# S_bus.net
KiCad netlist of a schematic drawn in Altium Designer
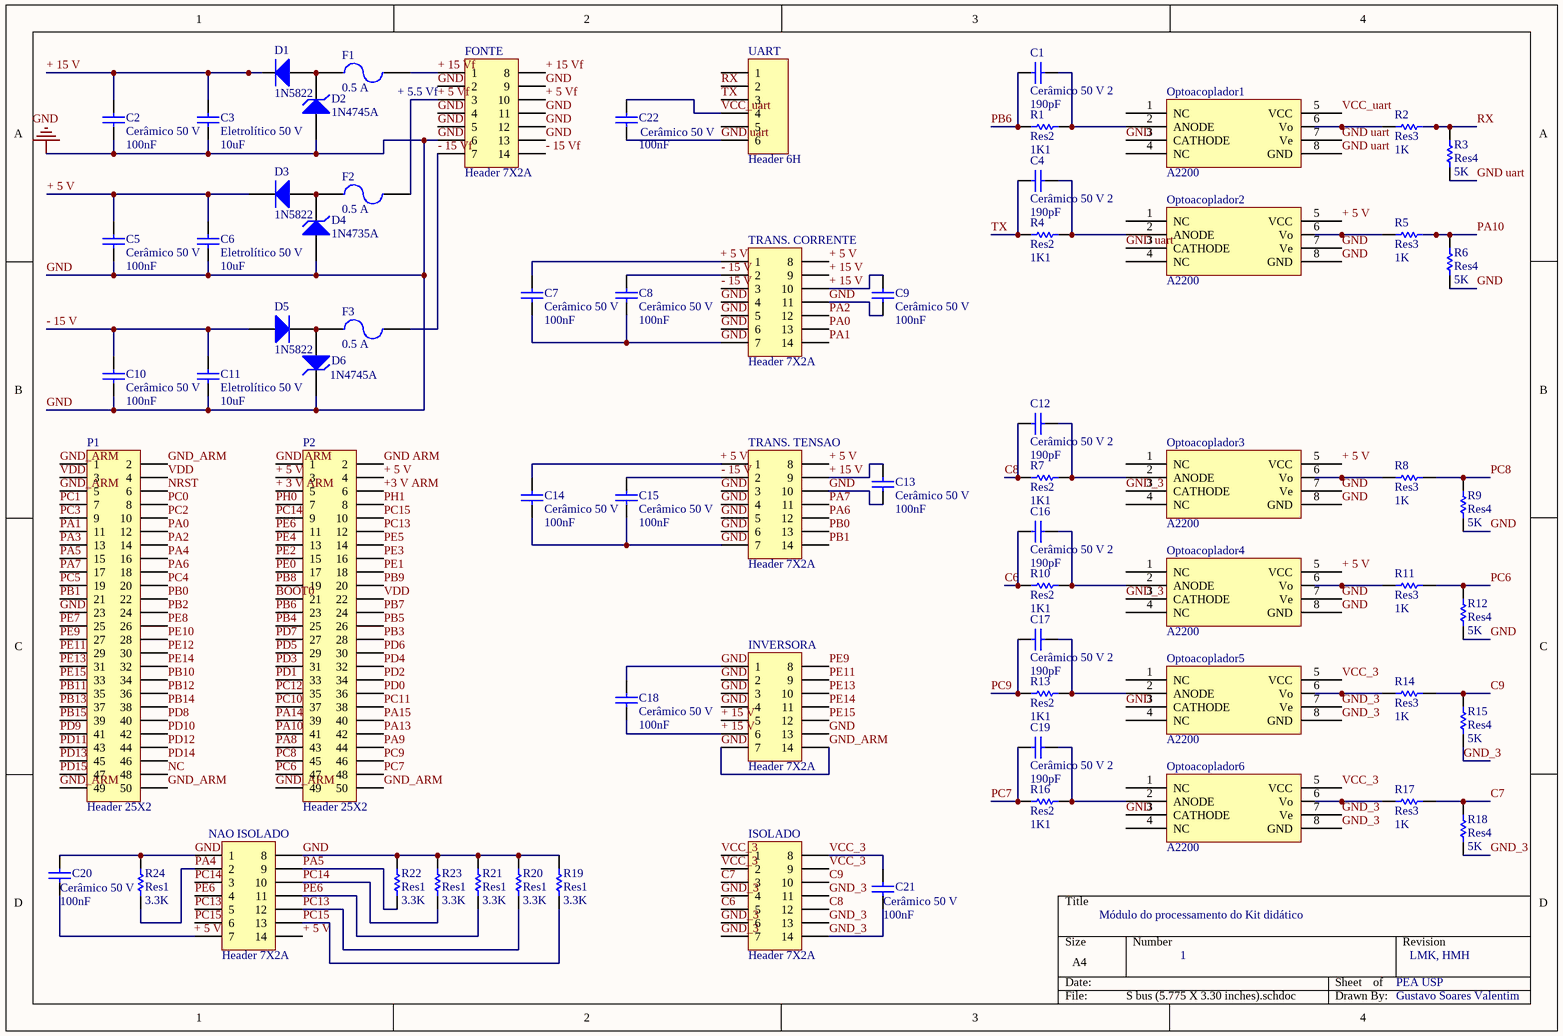
[diagram p0: S bus (5.775 X 3.30 inches).schdoc]

(export (version "E")
  (design (tool "Eeschema 10.0.6"))
  (components
    (comp (ref "C1")
      (value "Cerâmico 50 V 2")
      (footprint "RAD-0.2")
      (description "Capacitor")
      (fields (field (name "ALTIUM_VALUE") "190pF") (field (name "PUBLISHER") "Altium Limited"))
      (libsource (lib "Miscellaneous Devices") (part "Cap"))
    )
    (comp (ref "C2")
      (value "Cerâmico 50 V")
      (footprint "RAD-0.2")
      (description "Capacitor")
      (fields (field (name "ALTIUM_VALUE") "100nF") (field (name "PUBLISHER") "Altium Limited"))
      (libsource (lib "Miscellaneous Devices") (part "Cap"))
    )
    (comp (ref "C3")
      (value "Eletrolítico 50 V")
      (footprint "RB5-10.5")
      (description "Capacitor")
      (fields (field (name "ALTIUM_VALUE") "10uF") (field (name "PUBLISHER") "Altium Limited"))
      (libsource (lib "Miscellaneous Devices") (part "Cap"))
    )
    (comp (ref "C4")
      (value "Cerâmico 50 V 2")
      (footprint "RAD-0.2")
      (description "Capacitor")
      (fields (field (name "ALTIUM_VALUE") "190pF") (field (name "PUBLISHER") "Altium Limited"))
      (libsource (lib "Miscellaneous Devices") (part "Cap"))
    )
    (comp (ref "C5")
      (value "Cerâmico 50 V")
      (footprint "RAD-0.2")
      (description "Capacitor")
      (fields (field (name "ALTIUM_VALUE") "100nF") (field (name "PUBLISHER") "Altium Limited"))
      (libsource (lib "Miscellaneous Devices") (part "Cap"))
    )
    (comp (ref "C6")
      (value "Eletrolítico 50 V")
      (footprint "RB5-10.5")
      (description "Capacitor")
      (fields (field (name "ALTIUM_VALUE") "10uF") (field (name "PUBLISHER") "Altium Limited"))
      (libsource (lib "Miscellaneous Devices") (part "Cap"))
    )
    (comp (ref "C7")
      (value "Cerâmico 50 V")
      (footprint "RAD-0.2")
      (description "Capacitor")
      (fields (field (name "ALTIUM_VALUE") "100nF") (field (name "PUBLISHER") "Altium Limited"))
      (libsource (lib "Miscellaneous Devices") (part "Cap"))
    )
    (comp (ref "C8")
      (value "Cerâmico 50 V")
      (footprint "RAD-0.2")
      (description "Capacitor")
      (fields (field (name "ALTIUM_VALUE") "100nF") (field (name "PUBLISHER") "Altium Limited"))
      (libsource (lib "Miscellaneous Devices") (part "Cap"))
    )
    (comp (ref "C9")
      (value "Cerâmico 50 V")
      (footprint "RAD-0.2")
      (description "Capacitor")
      (fields (field (name "ALTIUM_VALUE") "100nF") (field (name "PUBLISHER") "Altium Limited"))
      (libsource (lib "Miscellaneous Devices") (part "Cap"))
    )
    (comp (ref "C10")
      (value "Cerâmico 50 V")
      (footprint "RAD-0.2")
      (description "Capacitor")
      (fields (field (name "ALTIUM_VALUE") "100nF") (field (name "PUBLISHER") "Altium Limited"))
      (libsource (lib "Miscellaneous Devices") (part "Cap"))
    )
    (comp (ref "C11")
      (value "Eletrolítico 50 V")
      (footprint "RB5-10.5")
      (description "Capacitor")
      (fields (field (name "ALTIUM_VALUE") "10uF") (field (name "PUBLISHER") "Altium Limited"))
      (libsource (lib "Miscellaneous Devices") (part "Cap"))
    )
    (comp (ref "C12")
      (value "Cerâmico 50 V 2")
      (footprint "RAD-0.2")
      (description "Capacitor")
      (fields (field (name "ALTIUM_VALUE") "190pF") (field (name "PUBLISHER") "Altium Limited"))
      (libsource (lib "Miscellaneous Devices") (part "Cap"))
    )
    (comp (ref "C13")
      (value "Cerâmico 50 V")
      (footprint "RAD-0.2")
      (description "Capacitor")
      (fields (field (name "ALTIUM_VALUE") "100nF") (field (name "PUBLISHER") "Altium Limited"))
      (libsource (lib "Miscellaneous Devices") (part "Cap"))
    )
    (comp (ref "C14")
      (value "Cerâmico 50 V")
      (footprint "RAD-0.2")
      (description "Capacitor")
      (fields (field (name "ALTIUM_VALUE") "100nF") (field (name "PUBLISHER") "Altium Limited"))
      (libsource (lib "Miscellaneous Devices") (part "Cap"))
    )
    (comp (ref "C15")
      (value "Cerâmico 50 V")
      (footprint "RAD-0.2")
      (description "Capacitor")
      (fields (field (name "ALTIUM_VALUE") "100nF") (field (name "PUBLISHER") "Altium Limited"))
      (libsource (lib "Miscellaneous Devices") (part "Cap"))
    )
    (comp (ref "C16")
      (value "Cerâmico 50 V 2")
      (footprint "RAD-0.2")
      (description "Capacitor")
      (fields (field (name "ALTIUM_VALUE") "190pF") (field (name "PUBLISHER") "Altium Limited"))
      (libsource (lib "Miscellaneous Devices") (part "Cap"))
    )
    (comp (ref "C17")
      (value "Cerâmico 50 V 2")
      (footprint "RAD-0.2")
      (description "Capacitor")
      (fields (field (name "ALTIUM_VALUE") "190pF") (field (name "PUBLISHER") "Altium Limited"))
      (libsource (lib "Miscellaneous Devices") (part "Cap"))
    )
    (comp (ref "C18")
      (value "Cerâmico 50 V")
      (footprint "RAD-0.2")
      (description "Capacitor")
      (fields (field (name "ALTIUM_VALUE") "100nF") (field (name "PUBLISHER") "Altium Limited"))
      (libsource (lib "Miscellaneous Devices") (part "Cap"))
    )
    (comp (ref "C19")
      (value "Cerâmico 50 V 2")
      (footprint "RAD-0.2")
      (description "Capacitor")
      (fields (field (name "ALTIUM_VALUE") "190pF") (field (name "PUBLISHER") "Altium Limited"))
      (libsource (lib "Miscellaneous Devices") (part "Cap"))
    )
    (comp (ref "C20")
      (value "Cerâmico 50 V")
      (footprint "RAD-0.2")
      (description "Capacitor")
      (fields (field (name "ALTIUM_VALUE") "100nF") (field (name "PUBLISHER") "Altium Limited"))
      (libsource (lib "Miscellaneous Devices") (part "Cap"))
    )
    (comp (ref "C21")
      (value "Cerâmico 50 V")
      (footprint "RAD-0.2")
      (description "Capacitor")
      (fields (field (name "ALTIUM_VALUE") "100nF") (field (name "PUBLISHER") "Altium Limited"))
      (libsource (lib "Miscellaneous Devices") (part "Cap"))
    )
    (comp (ref "C22")
      (value "Cerâmico 50 V")
      (footprint "RAD-0.2")
      (description "Capacitor")
      (fields (field (name "ALTIUM_VALUE") "100nF") (field (name "PUBLISHER") "Altium Limited"))
      (libsource (lib "Miscellaneous Devices") (part "Cap"))
    )
    (comp (ref "D1")
      (value "1N5822")
      (footprint "AXIAL-0.4")
      (description "Default Diode")
      (fields (field (name "PUBLISHER") "Altium Limited"))
      (libsource (lib "Miscellaneous Devices") (part "Diode"))
    )
    (comp (ref "D2")
      (value "1N4745A")
      (footprint "DIODE-0.4")
      (description "Zener Diode")
      (fields (field (name "PUBLISHER") "Altium Limited"))
      (libsource (lib "Miscellaneous Devices") (part "D Zener"))
    )
    (comp (ref "D3")
      (value "1N5822")
      (footprint "AXIAL-0.4")
      (description "Default Diode")
      (fields (field (name "PUBLISHER") "Altium Limited"))
      (libsource (lib "Miscellaneous Devices") (part "Diode"))
    )
    (comp (ref "D4")
      (value "1N4735A")
      (footprint "DIODE-0.4")
      (description "Zener Diode")
      (fields (field (name "PUBLISHER") "Altium Limited"))
      (libsource (lib "Miscellaneous Devices") (part "D Zener"))
    )
    (comp (ref "D5")
      (value "1N5822")
      (footprint "AXIAL-0.4")
      (description "Default Diode")
      (fields (field (name "PUBLISHER") "Altium Limited"))
      (libsource (lib "Miscellaneous Devices") (part "Diode"))
    )
    (comp (ref "D6")
      (value "1N4745A")
      (footprint "DIODE-0.4")
      (description "Zener Diode")
      (fields (field (name "PUBLISHER") "Altium Limited"))
      (libsource (lib "Miscellaneous Devices") (part "D Zener"))
    )
    (comp (ref "F1")
      (value "0.5 A")
      (footprint "Fusivel")
      (description "Fuse")
      (fields (field (name "PUBLISHER") "Altium Limited"))
      (libsource (lib "Miscellaneous Devices") (part "Fuse 2"))
    )
    (comp (ref "F2")
      (value "0.5 A")
      (footprint "Fusivel")
      (description "Fuse")
      (fields (field (name "PUBLISHER") "Altium Limited"))
      (libsource (lib "Miscellaneous Devices") (part "Fuse 2"))
    )
    (comp (ref "F3")
      (value "0.5 A")
      (footprint "Fusivel")
      (description "Fuse")
      (fields (field (name "PUBLISHER") "Altium Limited"))
      (libsource (lib "Miscellaneous Devices") (part "Fuse 2"))
    )
    (comp (ref "FONTE")
      (value "Header 7X2A")
      (footprint "HDR2X7_CEN")
      (description "Header, 7-Pin, Dual row")
      (fields (field (name "PUBLISHER") "Altium Limited"))
      (libsource (lib "Miscellaneous Connectors") (part "Header 7X2A"))
    )
    (comp (ref "INVERSORA")
      (value "Header 7X2A")
      (footprint "HDR2X7_CEN")
      (description "Header, 7-Pin, Dual row")
      (fields (field (name "PUBLISHER") "Altium Limited"))
      (libsource (lib "Miscellaneous Connectors") (part "Header 7X2A"))
    )
    (comp (ref "ISOLADO")
      (value "Header 7X2A")
      (footprint "HDR2X7_CEN")
      (description "Header, 7-Pin, Dual row")
      (fields (field (name "PUBLISHER") "Altium Limited"))
      (libsource (lib "Miscellaneous Connectors") (part "Header 7X2A"))
    )
    (comp (ref "NAO ISOLADO")
      (value "Header 7X2A")
      (footprint "HDR2X7_CEN")
      (description "Header, 7-Pin, Dual row")
      (fields (field (name "PUBLISHER") "Altium Limited"))
      (libsource (lib "Miscellaneous Connectors") (part "Header 7X2A"))
    )
    (comp (ref "Optoacoplador1")
      (value "A2200")
      (footprint "DIP8")
      (libsource (lib "optoacoplador") (part "Optoacoplador"))
    )
    (comp (ref "Optoacoplador2")
      (value "A2200")
      (footprint "DIP8")
      (libsource (lib "optoacoplador") (part "Optoacoplador"))
    )
    (comp (ref "Optoacoplador3")
      (value "A2200")
      (footprint "DIP8")
      (libsource (lib "optoacoplador") (part "Optoacoplador"))
    )
    (comp (ref "Optoacoplador4")
      (value "A2200")
      (footprint "DIP8")
      (libsource (lib "optoacoplador") (part "Optoacoplador"))
    )
    (comp (ref "Optoacoplador5")
      (value "A2200")
      (footprint "DIP8")
      (libsource (lib "optoacoplador") (part "Optoacoplador"))
    )
    (comp (ref "Optoacoplador6")
      (value "A2200")
      (footprint "DIP8")
      (libsource (lib "optoacoplador") (part "Optoacoplador"))
    )
    (comp (ref "P1")
      (value "Header 25X2")
      (footprint "HDR2X25")
      (description "Header, 25-Pin, Dual row")
      (fields (field (name "PUBLISHER") "Altium Limited"))
      (libsource (lib "Miscellaneous Connectors") (part "Header 25X2"))
    )
    (comp (ref "P2")
      (value "Header 25X2")
      (footprint "HDR2X25")
      (description "Header, 25-Pin, Dual row")
      (fields (field (name "PUBLISHER") "Altium Limited"))
      (libsource (lib "Miscellaneous Connectors") (part "Header 25X2"))
    )
    (comp (ref "R1")
      (value "Res2")
      (footprint "AXIAL-0.3")
      (description "Resistor")
      (fields (field (name "ALTIUM_VALUE") "1K1") (field (name "PUBLISHER") "Altium Limited"))
      (libsource (lib "Miscellaneous Devices") (part "Res1"))
    )
    (comp (ref "R2")
      (value "Res3")
      (footprint "AXIAL-0.3")
      (description "Resistor")
      (fields (field (name "ALTIUM_VALUE") "1K") (field (name "PUBLISHER") "Altium Limited"))
      (libsource (lib "Miscellaneous Devices") (part "Res1"))
    )
    (comp (ref "R3")
      (value "Res4")
      (footprint "AXIAL-0.3")
      (description "Resistor")
      (fields (field (name "ALTIUM_VALUE") "5K") (field (name "PUBLISHER") "Altium Limited"))
      (libsource (lib "Miscellaneous Devices") (part "Res1"))
    )
    (comp (ref "R4")
      (value "Res2")
      (footprint "AXIAL-0.3")
      (description "Resistor")
      (fields (field (name "ALTIUM_VALUE") "1K1") (field (name "PUBLISHER") "Altium Limited"))
      (libsource (lib "Miscellaneous Devices") (part "Res1"))
    )
    (comp (ref "R5")
      (value "Res3")
      (footprint "AXIAL-0.3")
      (description "Resistor")
      (fields (field (name "ALTIUM_VALUE") "1K") (field (name "PUBLISHER") "Altium Limited"))
      (libsource (lib "Miscellaneous Devices") (part "Res1"))
    )
    (comp (ref "R6")
      (value "Res4")
      (footprint "AXIAL-0.3")
      (description "Resistor")
      (fields (field (name "ALTIUM_VALUE") "5K") (field (name "PUBLISHER") "Altium Limited"))
      (libsource (lib "Miscellaneous Devices") (part "Res1"))
    )
    (comp (ref "R7")
      (value "Res2")
      (footprint "AXIAL-0.3")
      (description "Resistor")
      (fields (field (name "ALTIUM_VALUE") "1K1") (field (name "PUBLISHER") "Altium Limited"))
      (libsource (lib "Miscellaneous Devices") (part "Res1"))
    )
    (comp (ref "R8")
      (value "Res3")
      (footprint "AXIAL-0.3")
      (description "Resistor")
      (fields (field (name "ALTIUM_VALUE") "1K") (field (name "PUBLISHER") "Altium Limited"))
      (libsource (lib "Miscellaneous Devices") (part "Res1"))
    )
    (comp (ref "R9")
      (value "Res4")
      (footprint "AXIAL-0.3")
      (description "Resistor")
      (fields (field (name "ALTIUM_VALUE") "5K") (field (name "PUBLISHER") "Altium Limited"))
      (libsource (lib "Miscellaneous Devices") (part "Res1"))
    )
    (comp (ref "R10")
      (value "Res2")
      (footprint "AXIAL-0.3")
      (description "Resistor")
      (fields (field (name "ALTIUM_VALUE") "1K1") (field (name "PUBLISHER") "Altium Limited"))
      (libsource (lib "Miscellaneous Devices") (part "Res1"))
    )
    (comp (ref "R11")
      (value "Res3")
      (footprint "AXIAL-0.3")
      (description "Resistor")
      (fields (field (name "ALTIUM_VALUE") "1K") (field (name "PUBLISHER") "Altium Limited"))
      (libsource (lib "Miscellaneous Devices") (part "Res1"))
    )
    (comp (ref "R12")
      (value "Res4")
      (footprint "AXIAL-0.3")
      (description "Resistor")
      (fields (field (name "ALTIUM_VALUE") "5K") (field (name "PUBLISHER") "Altium Limited"))
      (libsource (lib "Miscellaneous Devices") (part "Res1"))
    )
    (comp (ref "R13")
      (value "Res2")
      (footprint "AXIAL-0.3")
      (description "Resistor")
      (fields (field (name "ALTIUM_VALUE") "1K1") (field (name "PUBLISHER") "Altium Limited"))
      (libsource (lib "Miscellaneous Devices") (part "Res1"))
    )
    (comp (ref "R14")
      (value "Res3")
      (footprint "AXIAL-0.3")
      (description "Resistor")
      (fields (field (name "ALTIUM_VALUE") "1K") (field (name "PUBLISHER") "Altium Limited"))
      (libsource (lib "Miscellaneous Devices") (part "Res1"))
    )
    (comp (ref "R15")
      (value "Res4")
      (footprint "AXIAL-0.3")
      (description "Resistor")
      (fields (field (name "ALTIUM_VALUE") "5K") (field (name "PUBLISHER") "Altium Limited"))
      (libsource (lib "Miscellaneous Devices") (part "Res1"))
    )
    (comp (ref "R16")
      (value "Res2")
      (footprint "AXIAL-0.3")
      (description "Resistor")
      (fields (field (name "ALTIUM_VALUE") "1K1") (field (name "PUBLISHER") "Altium Limited"))
      (libsource (lib "Miscellaneous Devices") (part "Res1"))
    )
    (comp (ref "R17")
      (value "Res3")
      (footprint "AXIAL-0.3")
      (description "Resistor")
      (fields (field (name "ALTIUM_VALUE") "1K") (field (name "PUBLISHER") "Altium Limited"))
      (libsource (lib "Miscellaneous Devices") (part "Res1"))
    )
    (comp (ref "R18")
      (value "Res4")
      (footprint "AXIAL-0.3")
      (description "Resistor")
      (fields (field (name "ALTIUM_VALUE") "5K") (field (name "PUBLISHER") "Altium Limited"))
      (libsource (lib "Miscellaneous Devices") (part "Res1"))
    )
    (comp (ref "R19")
      (value "Res1")
      (footprint "AXIAL-0.3")
      (description "Resistor")
      (fields (field (name "ALTIUM_VALUE") "3.3K") (field (name "PUBLISHER") "Altium Limited"))
      (libsource (lib "Miscellaneous Devices") (part "Res1"))
    )
    (comp (ref "R20")
      (value "Res1")
      (footprint "AXIAL-0.3")
      (description "Resistor")
      (fields (field (name "ALTIUM_VALUE") "3.3K") (field (name "PUBLISHER") "Altium Limited"))
      (libsource (lib "Miscellaneous Devices") (part "Res1"))
    )
    (comp (ref "R21")
      (value "Res1")
      (footprint "AXIAL-0.3")
      (description "Resistor")
      (fields (field (name "ALTIUM_VALUE") "3.3K") (field (name "PUBLISHER") "Altium Limited"))
      (libsource (lib "Miscellaneous Devices") (part "Res1"))
    )
    (comp (ref "R22")
      (value "Res1")
      (footprint "AXIAL-0.3")
      (description "Resistor")
      (fields (field (name "ALTIUM_VALUE") "3.3K") (field (name "PUBLISHER") "Altium Limited"))
      (libsource (lib "Miscellaneous Devices") (part "Res1"))
    )
    (comp (ref "R23")
      (value "Res1")
      (footprint "AXIAL-0.3")
      (description "Resistor")
      (fields (field (name "ALTIUM_VALUE") "3.3K") (field (name "PUBLISHER") "Altium Limited"))
      (libsource (lib "Miscellaneous Devices") (part "Res1"))
    )
    (comp (ref "R24")
      (value "Res1")
      (footprint "AXIAL-0.3")
      (description "Resistor")
      (fields (field (name "ALTIUM_VALUE") "3.3K") (field (name "PUBLISHER") "Altium Limited"))
      (libsource (lib "Miscellaneous Devices") (part "Res1"))
    )
    (comp (ref "TRANS. CORRENTE")
      (value "Header 7X2A")
      (footprint "HDR2X7_CEN")
      (description "Header, 7-Pin, Dual row")
      (fields (field (name "PUBLISHER") "Altium Limited"))
      (libsource (lib "Miscellaneous Connectors") (part "Header 7X2A"))
    )
    (comp (ref "TRANS. TENSAO")
      (value "Header 7X2A")
      (footprint "HDR2X7_CEN")
      (description "Header, 7-Pin, Dual row")
      (fields (field (name "PUBLISHER") "Altium Limited"))
      (libsource (lib "Miscellaneous Connectors") (part "Header 7X2A"))
    )
    (comp (ref "UART")
      (value "Header 6H")
      (footprint "HDR1X6")
      (description "Header, 6-Pin, Right Angle")
      (fields (field (name "PUBLISHER") "Altium Limited"))
      (libsource (lib "Miscellaneous Connectors") (part "Header 6H"))
    )
  )
  (nets
    (net (code "1") (name "/+ 3 V ARM") (class "Default")
      (node (ref "P2") (pin "5") (pinfunction "5_5") (pintype "passive"))
    )
    (net (code "2") (name "/+ 5 V") (class "Default")
      (node (ref "C14") (pin "2") (pinfunction "2_2") (pintype "passive"))
      (node (ref "C20") (pin "1") (pinfunction "1_1") (pintype "passive"))
      (node (ref "C5") (pin "2") (pinfunction "2_2") (pintype "passive"))
      (node (ref "C6") (pin "2") (pinfunction "2_2") (pintype "passive"))
      (node (ref "C7") (pin "2") (pinfunction "2_2") (pintype "passive"))
      (node (ref "D3") (pin "2") (pinfunction "K_2") (pintype "passive"))
      (node (ref "NAO ISOLADO") (pin "14") (pinfunction "14_14") (pintype "passive"))
      (node (ref "NAO ISOLADO") (pin "7") (pinfunction "7_7") (pintype "passive"))
      (node (ref "Optoacoplador2") (pin "5") (pinfunction "VCC_5") (pintype "passive"))
      (node (ref "Optoacoplador3") (pin "5") (pinfunction "VCC_5") (pintype "passive"))
      (node (ref "Optoacoplador4") (pin "5") (pinfunction "VCC_5") (pintype "passive"))
      (node (ref "P2") (pin "3") (pinfunction "3_3") (pintype "passive"))
      (node (ref "P2") (pin "4") (pinfunction "4_4") (pintype "passive"))
      (node (ref "TRANS. CORRENTE") (pin "1") (pinfunction "1_1") (pintype "passive"))
      (node (ref "TRANS. CORRENTE") (pin "8") (pinfunction "8_8") (pintype "passive"))
      (node (ref "TRANS. TENSAO") (pin "1") (pinfunction "1_1") (pintype "passive"))
      (node (ref "TRANS. TENSAO") (pin "8") (pinfunction "8_8") (pintype "passive"))
    )
    (net (code "3") (name "/+ 5 Vf") (class "Default")
      (node (ref "F2") (pin "2") (pinfunction "2_2") (pintype "passive"))
      (node (ref "FONTE") (pin "10") (pinfunction "10_10") (pintype "passive"))
      (node (ref "FONTE") (pin "3") (pinfunction "3_3") (pintype "passive"))
    )
    (net (code "4") (name "/+ 15 V") (class "Default")
      (node (ref "C13") (pin "2") (pinfunction "2_2") (pintype "passive"))
      (node (ref "C18") (pin "1") (pinfunction "1_1") (pintype "passive"))
      (node (ref "C2") (pin "2") (pinfunction "2_2") (pintype "passive"))
      (node (ref "C3") (pin "2") (pinfunction "2_2") (pintype "passive"))
      (node (ref "C9") (pin "2") (pinfunction "2_2") (pintype "passive"))
      (node (ref "D1") (pin "2") (pinfunction "K_2") (pintype "passive"))
      (node (ref "INVERSORA") (pin "5") (pinfunction "5_5") (pintype "passive"))
      (node (ref "INVERSORA") (pin "6") (pinfunction "6_6") (pintype "passive"))
      (node (ref "TRANS. CORRENTE") (pin "10") (pinfunction "10_10") (pintype "passive"))
      (node (ref "TRANS. CORRENTE") (pin "9") (pinfunction "9_9") (pintype "passive"))
      (node (ref "TRANS. TENSAO") (pin "9") (pinfunction "9_9") (pintype "passive"))
    )
    (net (code "5") (name "/+ 15 Vf") (class "Default")
      (node (ref "F1") (pin "2") (pinfunction "2_2") (pintype "passive"))
      (node (ref "FONTE") (pin "1") (pinfunction "1_1") (pintype "passive"))
      (node (ref "FONTE") (pin "8") (pinfunction "8_8") (pintype "passive"))
    )
    (net (code "6") (name "/+3 V ARM") (class "Default")
      (node (ref "P2") (pin "6") (pinfunction "6_6") (pintype "passive"))
    )
    (net (code "7") (name "/- 15 V") (class "Default")
      (node (ref "C10") (pin "2") (pinfunction "2_2") (pintype "passive"))
      (node (ref "C11") (pin "2") (pinfunction "2_2") (pintype "passive"))
      (node (ref "C15") (pin "2") (pinfunction "2_2") (pintype "passive"))
      (node (ref "C8") (pin "2") (pinfunction "2_2") (pintype "passive"))
      (node (ref "D5") (pin "1") (pinfunction "A_1") (pintype "passive"))
      (node (ref "TRANS. CORRENTE") (pin "2") (pinfunction "2_2") (pintype "passive"))
      (node (ref "TRANS. CORRENTE") (pin "3") (pinfunction "3_3") (pintype "passive"))
      (node (ref "TRANS. TENSAO") (pin "2") (pinfunction "2_2") (pintype "passive"))
    )
    (net (code "8") (name "/- 15 Vf") (class "Default")
      (node (ref "F3") (pin "2") (pinfunction "2_2") (pintype "passive"))
      (node (ref "FONTE") (pin "14") (pinfunction "14_14") (pintype "passive"))
      (node (ref "FONTE") (pin "7") (pinfunction "7_7") (pintype "passive"))
    )
    (net (code "10") (name "/BOOT0") (class "Default")
      (node (ref "P2") (pin "21") (pinfunction "21_21") (pintype "passive"))
    )
    (net (code "11") (name "/C6") (class "Default")
      (node (ref "C16") (pin "2") (pinfunction "2_2") (pintype "passive"))
      (node (ref "ISOLADO") (pin "5") (pinfunction "5_5") (pintype "passive"))
      (node (ref "R10") (pin "1") (pinfunction "1_1") (pintype "passive"))
    )
    (net (code "12") (name "/C7") (class "Default")
      (node (ref "ISOLADO") (pin "3") (pinfunction "3_3") (pintype "passive"))
      (node (ref "R17") (pin "2") (pinfunction "2_2") (pintype "passive"))
      (node (ref "R18") (pin "2") (pinfunction "2_2") (pintype "passive"))
    )
    (net (code "13") (name "/C8") (class "Default")
      (node (ref "C12") (pin "2") (pinfunction "2_2") (pintype "passive"))
      (node (ref "ISOLADO") (pin "12") (pinfunction "12_12") (pintype "passive"))
      (node (ref "R7") (pin "1") (pinfunction "1_1") (pintype "passive"))
    )
    (net (code "14") (name "/C9") (class "Default")
      (node (ref "ISOLADO") (pin "10") (pinfunction "10_10") (pintype "passive"))
      (node (ref "R14") (pin "2") (pinfunction "2_2") (pintype "passive"))
      (node (ref "R15") (pin "2") (pinfunction "2_2") (pintype "passive"))
    )
    (net (code "15") (name "/GND ARM") (class "Default")
      (node (ref "P2") (pin "1") (pinfunction "1_1") (pintype "passive"))
      (node (ref "P2") (pin "2") (pinfunction "2_2") (pintype "passive"))
    )
    (net (code "16") (name "/GND uart") (class "Default")
      (node (ref "C22") (pin "1") (pinfunction "1_1") (pintype "passive"))
      (node (ref "Optoacoplador1") (pin "7") (pinfunction "Ve_7") (pintype "passive"))
      (node (ref "Optoacoplador1") (pin "8") (pinfunction "GND_8") (pintype "passive"))
      (node (ref "Optoacoplador2") (pin "3") (pinfunction "CATHODE_3") (pintype "passive"))
      (node (ref "R3") (pin "1") (pinfunction "1_1") (pintype "passive"))
      (node (ref "UART") (pin "6") (pinfunction "6_6") (pintype "passive"))
    )
    (net (code "17") (name "/GND_3") (class "Default")
      (node (ref "C21") (pin "1") (pinfunction "1_1") (pintype "passive"))
      (node (ref "ISOLADO") (pin "11") (pinfunction "11_11") (pintype "passive"))
      (node (ref "ISOLADO") (pin "13") (pinfunction "13_13") (pintype "passive"))
      (node (ref "ISOLADO") (pin "14") (pinfunction "14_14") (pintype "passive"))
      (node (ref "ISOLADO") (pin "4") (pinfunction "4_4") (pintype "passive"))
      (node (ref "ISOLADO") (pin "6") (pinfunction "6_6") (pintype "passive"))
      (node (ref "ISOLADO") (pin "7") (pinfunction "7_7") (pintype "passive"))
      (node (ref "Optoacoplador3") (pin "3") (pinfunction "CATHODE_3") (pintype "passive"))
      (node (ref "Optoacoplador4") (pin "3") (pinfunction "CATHODE_3") (pintype "passive"))
      (node (ref "Optoacoplador5") (pin "7") (pinfunction "Ve_7") (pintype "passive"))
      (node (ref "Optoacoplador5") (pin "8") (pinfunction "GND_8") (pintype "passive"))
      (node (ref "Optoacoplador6") (pin "7") (pinfunction "Ve_7") (pintype "passive"))
      (node (ref "Optoacoplador6") (pin "8") (pinfunction "GND_8") (pintype "passive"))
      (node (ref "R15") (pin "1") (pinfunction "1_1") (pintype "passive"))
      (node (ref "R18") (pin "1") (pinfunction "1_1") (pintype "passive"))
    )
    (net (code "18") (name "/NC") (class "Default")
      (node (ref "P1") (pin "48") (pinfunction "48_48") (pintype "passive"))
    )
    (net (code "19") (name "/NRST") (class "Default")
      (node (ref "P1") (pin "6") (pinfunction "6_6") (pintype "passive"))
    )
    (net (code "20") (name "/PA0") (class "Default")
      (node (ref "P1") (pin "12") (pinfunction "12_12") (pintype "passive"))
      (node (ref "TRANS. CORRENTE") (pin "13") (pinfunction "13_13") (pintype "passive"))
    )
    (net (code "21") (name "/PA1") (class "Default")
      (node (ref "P1") (pin "11") (pinfunction "11_11") (pintype "passive"))
      (node (ref "TRANS. CORRENTE") (pin "14") (pinfunction "14_14") (pintype "passive"))
    )
    (net (code "22") (name "/PA2") (class "Default")
      (node (ref "P1") (pin "14") (pinfunction "14_14") (pintype "passive"))
      (node (ref "TRANS. CORRENTE") (pin "12") (pinfunction "12_12") (pintype "passive"))
    )
    (net (code "23") (name "/PA3") (class "Default")
      (node (ref "P1") (pin "13") (pinfunction "13_13") (pintype "passive"))
    )
    (net (code "24") (name "/PA4") (class "Default")
      (node (ref "NAO ISOLADO") (pin "2") (pinfunction "2_2") (pintype "passive"))
      (node (ref "P1") (pin "16") (pinfunction "16_16") (pintype "passive"))
      (node (ref "R24") (pin "1") (pinfunction "1_1") (pintype "passive"))
    )
    (net (code "25") (name "/PA5") (class "Default")
      (node (ref "NAO ISOLADO") (pin "9") (pinfunction "9_9") (pintype "passive"))
      (node (ref "P1") (pin "15") (pinfunction "15_15") (pintype "passive"))
      (node (ref "R22") (pin "1") (pinfunction "1_1") (pintype "passive"))
    )
    (net (code "26") (name "/PA6") (class "Default")
      (node (ref "P1") (pin "18") (pinfunction "18_18") (pintype "passive"))
      (node (ref "TRANS. TENSAO") (pin "12") (pinfunction "12_12") (pintype "passive"))
    )
    (net (code "27") (name "/PA7") (class "Default")
      (node (ref "P1") (pin "17") (pinfunction "17_17") (pintype "passive"))
      (node (ref "TRANS. TENSAO") (pin "11") (pinfunction "11_11") (pintype "passive"))
    )
    (net (code "28") (name "/PA8") (class "Default")
      (node (ref "P2") (pin "43") (pinfunction "43_43") (pintype "passive"))
    )
    (net (code "29") (name "/PA9") (class "Default")
      (node (ref "P2") (pin "44") (pinfunction "44_44") (pintype "passive"))
    )
    (net (code "30") (name "/PA10") (class "Default")
      (node (ref "P2") (pin "41") (pinfunction "41_41") (pintype "passive"))
      (node (ref "R5") (pin "2") (pinfunction "2_2") (pintype "passive"))
      (node (ref "R6") (pin "2") (pinfunction "2_2") (pintype "passive"))
    )
    (net (code "31") (name "/PA13") (class "Default")
      (node (ref "P2") (pin "42") (pinfunction "42_42") (pintype "passive"))
    )
    (net (code "32") (name "/PA14") (class "Default")
      (node (ref "P2") (pin "39") (pinfunction "39_39") (pintype "passive"))
    )
    (net (code "33") (name "/PA15") (class "Default")
      (node (ref "P2") (pin "40") (pinfunction "40_40") (pintype "passive"))
    )
    (net (code "34") (name "/PB0") (class "Default")
      (node (ref "P1") (pin "22") (pinfunction "22_22") (pintype "passive"))
      (node (ref "TRANS. TENSAO") (pin "13") (pinfunction "13_13") (pintype "passive"))
    )
    (net (code "35") (name "/PB1") (class "Default")
      (node (ref "P1") (pin "21") (pinfunction "21_21") (pintype "passive"))
      (node (ref "TRANS. TENSAO") (pin "14") (pinfunction "14_14") (pintype "passive"))
    )
    (net (code "36") (name "/PB2") (class "Default")
      (node (ref "P1") (pin "24") (pinfunction "24_24") (pintype "passive"))
    )
    (net (code "37") (name "/PB3") (class "Default")
      (node (ref "P2") (pin "28") (pinfunction "28_28") (pintype "passive"))
    )
    (net (code "38") (name "/PB4") (class "Default")
      (node (ref "P2") (pin "25") (pinfunction "25_25") (pintype "passive"))
    )
    (net (code "39") (name "/PB5") (class "Default")
      (node (ref "P2") (pin "26") (pinfunction "26_26") (pintype "passive"))
    )
    (net (code "40") (name "/PB6") (class "Default")
      (node (ref "C1") (pin "2") (pinfunction "2_2") (pintype "passive"))
      (node (ref "P2") (pin "23") (pinfunction "23_23") (pintype "passive"))
      (node (ref "R1") (pin "1") (pinfunction "1_1") (pintype "passive"))
    )
    (net (code "41") (name "/PB7") (class "Default")
      (node (ref "P2") (pin "24") (pinfunction "24_24") (pintype "passive"))
    )
    (net (code "42") (name "/PB8") (class "Default")
      (node (ref "P2") (pin "19") (pinfunction "19_19") (pintype "passive"))
    )
    (net (code "43") (name "/PB9") (class "Default")
      (node (ref "P2") (pin "20") (pinfunction "20_20") (pintype "passive"))
    )
    (net (code "44") (name "/PB10") (class "Default")
      (node (ref "P1") (pin "34") (pinfunction "34_34") (pintype "passive"))
    )
    (net (code "45") (name "/PB11") (class "Default")
      (node (ref "P1") (pin "35") (pinfunction "35_35") (pintype "passive"))
    )
    (net (code "46") (name "/PB12") (class "Default")
      (node (ref "P1") (pin "36") (pinfunction "36_36") (pintype "passive"))
    )
    (net (code "47") (name "/PB13") (class "Default")
      (node (ref "P1") (pin "37") (pinfunction "37_37") (pintype "passive"))
    )
    (net (code "48") (name "/PB14") (class "Default")
      (node (ref "P1") (pin "38") (pinfunction "38_38") (pintype "passive"))
    )
    (net (code "49") (name "/PB15") (class "Default")
      (node (ref "P1") (pin "39") (pinfunction "39_39") (pintype "passive"))
    )
    (net (code "50") (name "/PC0") (class "Default")
      (node (ref "P1") (pin "8") (pinfunction "8_8") (pintype "passive"))
    )
    (net (code "51") (name "/PC1") (class "Default")
      (node (ref "P1") (pin "7") (pinfunction "7_7") (pintype "passive"))
    )
    (net (code "52") (name "/PC2") (class "Default")
      (node (ref "P1") (pin "10") (pinfunction "10_10") (pintype "passive"))
    )
    (net (code "53") (name "/PC3") (class "Default")
      (node (ref "P1") (pin "9") (pinfunction "9_9") (pintype "passive"))
    )
    (net (code "54") (name "/PC4") (class "Default")
      (node (ref "P1") (pin "20") (pinfunction "20_20") (pintype "passive"))
    )
    (net (code "55") (name "/PC5") (class "Default")
      (node (ref "P1") (pin "19") (pinfunction "19_19") (pintype "passive"))
    )
    (net (code "56") (name "/PC6") (class "Default")
      (node (ref "P2") (pin "47") (pinfunction "47_47") (pintype "passive"))
      (node (ref "R11") (pin "2") (pinfunction "2_2") (pintype "passive"))
      (node (ref "R12") (pin "2") (pinfunction "2_2") (pintype "passive"))
    )
    (net (code "57") (name "/PC7") (class "Default")
      (node (ref "C19") (pin "2") (pinfunction "2_2") (pintype "passive"))
      (node (ref "P2") (pin "48") (pinfunction "48_48") (pintype "passive"))
      (node (ref "R16") (pin "1") (pinfunction "1_1") (pintype "passive"))
    )
    (net (code "58") (name "/PC8") (class "Default")
      (node (ref "P2") (pin "45") (pinfunction "45_45") (pintype "passive"))
      (node (ref "R8") (pin "2") (pinfunction "2_2") (pintype "passive"))
      (node (ref "R9") (pin "2") (pinfunction "2_2") (pintype "passive"))
    )
    (net (code "59") (name "/PC9") (class "Default")
      (node (ref "C17") (pin "2") (pinfunction "2_2") (pintype "passive"))
      (node (ref "P2") (pin "46") (pinfunction "46_46") (pintype "passive"))
      (node (ref "R13") (pin "1") (pinfunction "1_1") (pintype "passive"))
    )
    (net (code "60") (name "/PC10") (class "Default")
      (node (ref "P2") (pin "37") (pinfunction "37_37") (pintype "passive"))
    )
    (net (code "61") (name "/PC11") (class "Default")
      (node (ref "P2") (pin "38") (pinfunction "38_38") (pintype "passive"))
    )
    (net (code "62") (name "/PC12") (class "Default")
      (node (ref "P2") (pin "35") (pinfunction "35_35") (pintype "passive"))
    )
    (net (code "63") (name "/PC13") (class "Default")
      (node (ref "NAO ISOLADO") (pin "12") (pinfunction "12_12") (pintype "passive"))
      (node (ref "NAO ISOLADO") (pin "5") (pinfunction "5_5") (pintype "passive"))
      (node (ref "P2") (pin "12") (pinfunction "12_12") (pintype "passive"))
      (node (ref "R20") (pin "1") (pinfunction "1_1") (pintype "passive"))
    )
    (net (code "64") (name "/PC14") (class "Default")
      (node (ref "NAO ISOLADO") (pin "10") (pinfunction "10_10") (pintype "passive"))
      (node (ref "NAO ISOLADO") (pin "3") (pinfunction "3_3") (pintype "passive"))
      (node (ref "P2") (pin "9") (pinfunction "9_9") (pintype "passive"))
      (node (ref "R23") (pin "1") (pinfunction "1_1") (pintype "passive"))
    )
    (net (code "65") (name "/PC15") (class "Default")
      (node (ref "NAO ISOLADO") (pin "13") (pinfunction "13_13") (pintype "passive"))
      (node (ref "NAO ISOLADO") (pin "6") (pinfunction "6_6") (pintype "passive"))
      (node (ref "P2") (pin "10") (pinfunction "10_10") (pintype "passive"))
      (node (ref "R19") (pin "1") (pinfunction "1_1") (pintype "passive"))
    )
    (net (code "66") (name "/PD0") (class "Default")
      (node (ref "P2") (pin "36") (pinfunction "36_36") (pintype "passive"))
    )
    (net (code "67") (name "/PD1") (class "Default")
      (node (ref "P2") (pin "33") (pinfunction "33_33") (pintype "passive"))
    )
    (net (code "68") (name "/PD2") (class "Default")
      (node (ref "P2") (pin "34") (pinfunction "34_34") (pintype "passive"))
    )
    (net (code "69") (name "/PD3") (class "Default")
      (node (ref "P2") (pin "31") (pinfunction "31_31") (pintype "passive"))
    )
    (net (code "70") (name "/PD4") (class "Default")
      (node (ref "P2") (pin "32") (pinfunction "32_32") (pintype "passive"))
    )
    (net (code "71") (name "/PD5") (class "Default")
      (node (ref "P2") (pin "29") (pinfunction "29_29") (pintype "passive"))
    )
    (net (code "72") (name "/PD6") (class "Default")
      (node (ref "P2") (pin "30") (pinfunction "30_30") (pintype "passive"))
    )
    (net (code "73") (name "/PD7") (class "Default")
      (node (ref "P2") (pin "27") (pinfunction "27_27") (pintype "passive"))
    )
    (net (code "74") (name "/PD8") (class "Default")
      (node (ref "P1") (pin "40") (pinfunction "40_40") (pintype "passive"))
    )
    (net (code "75") (name "/PD9") (class "Default")
      (node (ref "P1") (pin "41") (pinfunction "41_41") (pintype "passive"))
    )
    (net (code "76") (name "/PD10") (class "Default")
      (node (ref "P1") (pin "42") (pinfunction "42_42") (pintype "passive"))
    )
    (net (code "77") (name "/PD11") (class "Default")
      (node (ref "P1") (pin "43") (pinfunction "43_43") (pintype "passive"))
    )
    (net (code "78") (name "/PD12") (class "Default")
      (node (ref "P1") (pin "44") (pinfunction "44_44") (pintype "passive"))
    )
    (net (code "79") (name "/PD13") (class "Default")
      (node (ref "P1") (pin "45") (pinfunction "45_45") (pintype "passive"))
    )
    (net (code "80") (name "/PD14") (class "Default")
      (node (ref "P1") (pin "46") (pinfunction "46_46") (pintype "passive"))
    )
    (net (code "81") (name "/PD15") (class "Default")
      (node (ref "P1") (pin "47") (pinfunction "47_47") (pintype "passive"))
    )
    (net (code "82") (name "/PE0") (class "Default")
      (node (ref "P2") (pin "17") (pinfunction "17_17") (pintype "passive"))
    )
    (net (code "83") (name "/PE1") (class "Default")
      (node (ref "P2") (pin "18") (pinfunction "18_18") (pintype "passive"))
    )
    (net (code "84") (name "/PE2") (class "Default")
      (node (ref "P2") (pin "15") (pinfunction "15_15") (pintype "passive"))
    )
    (net (code "85") (name "/PE3") (class "Default")
      (node (ref "P2") (pin "16") (pinfunction "16_16") (pintype "passive"))
    )
    (net (code "86") (name "/PE4") (class "Default")
      (node (ref "P2") (pin "13") (pinfunction "13_13") (pintype "passive"))
    )
    (net (code "87") (name "/PE5") (class "Default")
      (node (ref "P2") (pin "14") (pinfunction "14_14") (pintype "passive"))
    )
    (net (code "88") (name "/PE6") (class "Default")
      (node (ref "NAO ISOLADO") (pin "11") (pinfunction "11_11") (pintype "passive"))
      (node (ref "NAO ISOLADO") (pin "4") (pinfunction "4_4") (pintype "passive"))
      (node (ref "P2") (pin "11") (pinfunction "11_11") (pintype "passive"))
      (node (ref "R21") (pin "1") (pinfunction "1_1") (pintype "passive"))
    )
    (net (code "89") (name "/PE7") (class "Default")
      (node (ref "P1") (pin "25") (pinfunction "25_25") (pintype "passive"))
    )
    (net (code "90") (name "/PE8") (class "Default")
      (node (ref "P1") (pin "26") (pinfunction "26_26") (pintype "passive"))
    )
    (net (code "91") (name "/PE9") (class "Default")
      (node (ref "INVERSORA") (pin "8") (pinfunction "8_8") (pintype "passive"))
      (node (ref "P1") (pin "27") (pinfunction "27_27") (pintype "passive"))
    )
    (net (code "92") (name "/PE10") (class "Default")
      (node (ref "P1") (pin "28") (pinfunction "28_28") (pintype "passive"))
    )
    (net (code "93") (name "/PE11") (class "Default")
      (node (ref "INVERSORA") (pin "9") (pinfunction "9_9") (pintype "passive"))
      (node (ref "P1") (pin "29") (pinfunction "29_29") (pintype "passive"))
    )
    (net (code "94") (name "/PE12") (class "Default")
      (node (ref "P1") (pin "30") (pinfunction "30_30") (pintype "passive"))
    )
    (net (code "95") (name "/PE13") (class "Default")
      (node (ref "INVERSORA") (pin "10") (pinfunction "10_10") (pintype "passive"))
      (node (ref "P1") (pin "31") (pinfunction "31_31") (pintype "passive"))
    )
    (net (code "96") (name "/PE14") (class "Default")
      (node (ref "INVERSORA") (pin "11") (pinfunction "11_11") (pintype "passive"))
      (node (ref "P1") (pin "32") (pinfunction "32_32") (pintype "passive"))
    )
    (net (code "97") (name "/PE15") (class "Default")
      (node (ref "INVERSORA") (pin "12") (pinfunction "12_12") (pintype "passive"))
      (node (ref "P1") (pin "33") (pinfunction "33_33") (pintype "passive"))
    )
    (net (code "98") (name "/PH0") (class "Default")
      (node (ref "P2") (pin "7") (pinfunction "7_7") (pintype "passive"))
    )
    (net (code "99") (name "/PH1") (class "Default")
      (node (ref "P2") (pin "8") (pinfunction "8_8") (pintype "passive"))
    )
    (net (code "100") (name "/RX") (class "Default")
      (node (ref "R2") (pin "2") (pinfunction "2_2") (pintype "passive"))
      (node (ref "R3") (pin "2") (pinfunction "2_2") (pintype "passive"))
      (node (ref "UART") (pin "2") (pinfunction "2_2") (pintype "passive"))
    )
    (net (code "101") (name "/TX") (class "Default")
      (node (ref "C4") (pin "2") (pinfunction "2_2") (pintype "passive"))
      (node (ref "R4") (pin "1") (pinfunction "1_1") (pintype "passive"))
      (node (ref "UART") (pin "3") (pinfunction "3_3") (pintype "passive"))
    )
    (net (code "102") (name "/VCC_3") (class "Default")
      (node (ref "C21") (pin "2") (pinfunction "2_2") (pintype "passive"))
      (node (ref "ISOLADO") (pin "1") (pinfunction "1_1") (pintype "passive"))
      (node (ref "ISOLADO") (pin "2") (pinfunction "2_2") (pintype "passive"))
      (node (ref "ISOLADO") (pin "8") (pinfunction "8_8") (pintype "passive"))
      (node (ref "ISOLADO") (pin "9") (pinfunction "9_9") (pintype "passive"))
      (node (ref "Optoacoplador5") (pin "5") (pinfunction "VCC_5") (pintype "passive"))
      (node (ref "Optoacoplador6") (pin "5") (pinfunction "VCC_5") (pintype "passive"))
    )
    (net (code "103") (name "/VCC_uart") (class "Default")
      (node (ref "C22") (pin "2") (pinfunction "2_2") (pintype "passive"))
      (node (ref "Optoacoplador1") (pin "5") (pinfunction "VCC_5") (pintype "passive"))
      (node (ref "UART") (pin "4") (pinfunction "4_4") (pintype "passive"))
    )
    (net (code "104") (name "/VDD") (class "Default")
      (node (ref "P1") (pin "3") (pinfunction "3_3") (pintype "passive"))
      (node (ref "P1") (pin "4") (pinfunction "4_4") (pintype "passive"))
      (node (ref "P2") (pin "22") (pinfunction "22_22") (pintype "passive"))
    )
    (net (code "105") (name "GND") (class "Default")
      (node (ref "C10") (pin "1") (pinfunction "1_1") (pintype "passive"))
      (node (ref "C11") (pin "1") (pinfunction "1_1") (pintype "passive"))
      (node (ref "C13") (pin "1") (pinfunction "1_1") (pintype "passive"))
      (node (ref "C14") (pin "1") (pinfunction "1_1") (pintype "passive"))
      (node (ref "C15") (pin "1") (pinfunction "1_1") (pintype "passive"))
      (node (ref "C18") (pin "2") (pinfunction "2_2") (pintype "passive"))
      (node (ref "C2") (pin "1") (pinfunction "1_1") (pintype "passive"))
      (node (ref "C20") (pin "2") (pinfunction "2_2") (pintype "passive"))
      (node (ref "C3") (pin "1") (pinfunction "1_1") (pintype "passive"))
      (node (ref "C5") (pin "1") (pinfunction "1_1") (pintype "passive"))
      (node (ref "C6") (pin "1") (pinfunction "1_1") (pintype "passive"))
      (node (ref "C7") (pin "1") (pinfunction "1_1") (pintype "passive"))
      (node (ref "C8") (pin "1") (pinfunction "1_1") (pintype "passive"))
      (node (ref "C9") (pin "1") (pinfunction "1_1") (pintype "passive"))
      (node (ref "D2") (pin "1") (pinfunction "A_1") (pintype "passive"))
      (node (ref "D4") (pin "1") (pinfunction "A_1") (pintype "passive"))
      (node (ref "D6") (pin "2") (pinfunction "K_2") (pintype "passive"))
      (node (ref "FONTE") (pin "11") (pinfunction "11_11") (pintype "passive"))
      (node (ref "FONTE") (pin "12") (pinfunction "12_12") (pintype "passive"))
      (node (ref "FONTE") (pin "13") (pinfunction "13_13") (pintype "passive"))
      (node (ref "FONTE") (pin "2") (pinfunction "2_2") (pintype "passive"))
      (node (ref "FONTE") (pin "4") (pinfunction "4_4") (pintype "passive"))
      (node (ref "FONTE") (pin "5") (pinfunction "5_5") (pintype "passive"))
      (node (ref "FONTE") (pin "6") (pinfunction "6_6") (pintype "passive"))
      (node (ref "FONTE") (pin "9") (pinfunction "9_9") (pintype "passive"))
      (node (ref "INVERSORA") (pin "1") (pinfunction "1_1") (pintype "passive"))
      (node (ref "INVERSORA") (pin "13") (pinfunction "13_13") (pintype "passive"))
      (node (ref "INVERSORA") (pin "14") (pinfunction "14_14") (pintype "passive"))
      (node (ref "INVERSORA") (pin "2") (pinfunction "2_2") (pintype "passive"))
      (node (ref "INVERSORA") (pin "3") (pinfunction "3_3") (pintype "passive"))
      (node (ref "INVERSORA") (pin "4") (pinfunction "4_4") (pintype "passive"))
      (node (ref "INVERSORA") (pin "7") (pinfunction "7_7") (pintype "passive"))
      (node (ref "NAO ISOLADO") (pin "1") (pinfunction "1_1") (pintype "passive"))
      (node (ref "NAO ISOLADO") (pin "8") (pinfunction "8_8") (pintype "passive"))
      (node (ref "Optoacoplador1") (pin "3") (pinfunction "CATHODE_3") (pintype "passive"))
      (node (ref "Optoacoplador2") (pin "7") (pinfunction "Ve_7") (pintype "passive"))
      (node (ref "Optoacoplador2") (pin "8") (pinfunction "GND_8") (pintype "passive"))
      (node (ref "Optoacoplador3") (pin "7") (pinfunction "Ve_7") (pintype "passive"))
      (node (ref "Optoacoplador3") (pin "8") (pinfunction "GND_8") (pintype "passive"))
      (node (ref "Optoacoplador4") (pin "7") (pinfunction "Ve_7") (pintype "passive"))
      (node (ref "Optoacoplador4") (pin "8") (pinfunction "GND_8") (pintype "passive"))
      (node (ref "Optoacoplador5") (pin "3") (pinfunction "CATHODE_3") (pintype "passive"))
      (node (ref "Optoacoplador6") (pin "3") (pinfunction "CATHODE_3") (pintype "passive"))
      (node (ref "P1") (pin "1") (pinfunction "1_1") (pintype "passive"))
      (node (ref "P1") (pin "2") (pinfunction "2_2") (pintype "passive"))
      (node (ref "P1") (pin "23") (pinfunction "23_23") (pintype "passive"))
      (node (ref "P1") (pin "49") (pinfunction "49_49") (pintype "passive"))
      (node (ref "P1") (pin "5") (pinfunction "5_5") (pintype "passive"))
      (node (ref "P1") (pin "50") (pinfunction "50_50") (pintype "passive"))
      (node (ref "P2") (pin "49") (pinfunction "49_49") (pintype "passive"))
      (node (ref "P2") (pin "50") (pinfunction "50_50") (pintype "passive"))
      (node (ref "R12") (pin "1") (pinfunction "1_1") (pintype "passive"))
      (node (ref "R19") (pin "2") (pinfunction "2_2") (pintype "passive"))
      (node (ref "R20") (pin "2") (pinfunction "2_2") (pintype "passive"))
      (node (ref "R21") (pin "2") (pinfunction "2_2") (pintype "passive"))
      (node (ref "R22") (pin "2") (pinfunction "2_2") (pintype "passive"))
      (node (ref "R23") (pin "2") (pinfunction "2_2") (pintype "passive"))
      (node (ref "R24") (pin "2") (pinfunction "2_2") (pintype "passive"))
      (node (ref "R6") (pin "1") (pinfunction "1_1") (pintype "passive"))
      (node (ref "R9") (pin "1") (pinfunction "1_1") (pintype "passive"))
      (node (ref "TRANS. CORRENTE") (pin "11") (pinfunction "11_11") (pintype "passive"))
      (node (ref "TRANS. CORRENTE") (pin "4") (pinfunction "4_4") (pintype "passive"))
      (node (ref "TRANS. CORRENTE") (pin "5") (pinfunction "5_5") (pintype "passive"))
      (node (ref "TRANS. CORRENTE") (pin "6") (pinfunction "6_6") (pintype "passive"))
      (node (ref "TRANS. CORRENTE") (pin "7") (pinfunction "7_7") (pintype "passive"))
      (node (ref "TRANS. TENSAO") (pin "10") (pinfunction "10_10") (pintype "passive"))
      (node (ref "TRANS. TENSAO") (pin "3") (pinfunction "3_3") (pintype "passive"))
      (node (ref "TRANS. TENSAO") (pin "4") (pinfunction "4_4") (pintype "passive"))
      (node (ref "TRANS. TENSAO") (pin "5") (pinfunction "5_5") (pintype "passive"))
      (node (ref "TRANS. TENSAO") (pin "6") (pinfunction "6_6") (pintype "passive"))
      (node (ref "TRANS. TENSAO") (pin "7") (pinfunction "7_7") (pintype "passive"))
    )
    (net (code "106") (name "Net-(D1-A)") (class "Default")
      (node (ref "D1") (pin "1") (pinfunction "A_1") (pintype "passive"))
      (node (ref "D2") (pin "2") (pinfunction "K_2") (pintype "passive"))
      (node (ref "F1") (pin "1") (pinfunction "1_1") (pintype "passive"))
    )
    (net (code "107") (name "Net-(D3-A)") (class "Default")
      (node (ref "D3") (pin "1") (pinfunction "A_1") (pintype "passive"))
      (node (ref "D4") (pin "2") (pinfunction "K_2") (pintype "passive"))
      (node (ref "F2") (pin "1") (pinfunction "1_1") (pintype "passive"))
    )
    (net (code "108") (name "Net-(D5-K)") (class "Default")
      (node (ref "D5") (pin "2") (pinfunction "K_2") (pintype "passive"))
      (node (ref "D6") (pin "1") (pinfunction "A_1") (pintype "passive"))
      (node (ref "F3") (pin "1") (pinfunction "1_1") (pintype "passive"))
    )
    (net (code "109") (name "Net-(Optoacoplador1-ANODE)") (class "Default")
      (node (ref "C1") (pin "1") (pinfunction "1_1") (pintype "passive"))
      (node (ref "Optoacoplador1") (pin "2") (pinfunction "ANODE_2") (pintype "passive"))
      (node (ref "R1") (pin "2") (pinfunction "2_2") (pintype "passive"))
    )
    (net (code "110") (name "Net-(Optoacoplador1-Vo)") (class "Default")
      (node (ref "Optoacoplador1") (pin "6") (pinfunction "Vo_6") (pintype "passive"))
      (node (ref "R2") (pin "1") (pinfunction "1_1") (pintype "passive"))
    )
    (net (code "111") (name "Net-(Optoacoplador2-ANODE)") (class "Default")
      (node (ref "C4") (pin "1") (pinfunction "1_1") (pintype "passive"))
      (node (ref "Optoacoplador2") (pin "2") (pinfunction "ANODE_2") (pintype "passive"))
      (node (ref "R4") (pin "2") (pinfunction "2_2") (pintype "passive"))
    )
    (net (code "112") (name "Net-(Optoacoplador2-Vo)") (class "Default")
      (node (ref "Optoacoplador2") (pin "6") (pinfunction "Vo_6") (pintype "passive"))
      (node (ref "R5") (pin "1") (pinfunction "1_1") (pintype "passive"))
    )
    (net (code "113") (name "Net-(Optoacoplador3-ANODE)") (class "Default")
      (node (ref "C12") (pin "1") (pinfunction "1_1") (pintype "passive"))
      (node (ref "Optoacoplador3") (pin "2") (pinfunction "ANODE_2") (pintype "passive"))
      (node (ref "R7") (pin "2") (pinfunction "2_2") (pintype "passive"))
    )
    (net (code "114") (name "Net-(Optoacoplador3-Vo)") (class "Default")
      (node (ref "Optoacoplador3") (pin "6") (pinfunction "Vo_6") (pintype "passive"))
      (node (ref "R8") (pin "1") (pinfunction "1_1") (pintype "passive"))
    )
    (net (code "115") (name "Net-(Optoacoplador4-ANODE)") (class "Default")
      (node (ref "C16") (pin "1") (pinfunction "1_1") (pintype "passive"))
      (node (ref "Optoacoplador4") (pin "2") (pinfunction "ANODE_2") (pintype "passive"))
      (node (ref "R10") (pin "2") (pinfunction "2_2") (pintype "passive"))
    )
    (net (code "116") (name "Net-(Optoacoplador4-Vo)") (class "Default")
      (node (ref "Optoacoplador4") (pin "6") (pinfunction "Vo_6") (pintype "passive"))
      (node (ref "R11") (pin "1") (pinfunction "1_1") (pintype "passive"))
    )
    (net (code "117") (name "Net-(Optoacoplador5-ANODE)") (class "Default")
      (node (ref "C17") (pin "1") (pinfunction "1_1") (pintype "passive"))
      (node (ref "Optoacoplador5") (pin "2") (pinfunction "ANODE_2") (pintype "passive"))
      (node (ref "R13") (pin "2") (pinfunction "2_2") (pintype "passive"))
    )
    (net (code "118") (name "Net-(Optoacoplador5-Vo)") (class "Default")
      (node (ref "Optoacoplador5") (pin "6") (pinfunction "Vo_6") (pintype "passive"))
      (node (ref "R14") (pin "1") (pinfunction "1_1") (pintype "passive"))
    )
    (net (code "119") (name "Net-(Optoacoplador6-ANODE)") (class "Default")
      (node (ref "C19") (pin "1") (pinfunction "1_1") (pintype "passive"))
      (node (ref "Optoacoplador6") (pin "2") (pinfunction "ANODE_2") (pintype "passive"))
      (node (ref "R16") (pin "2") (pinfunction "2_2") (pintype "passive"))
    )
    (net (code "120") (name "Net-(Optoacoplador6-Vo)") (class "Default")
      (node (ref "Optoacoplador6") (pin "6") (pinfunction "Vo_6") (pintype "passive"))
      (node (ref "R17") (pin "1") (pinfunction "1_1") (pintype "passive"))
    )
    (net (code "121") (name "unconnected-(Optoacoplador1-NC-Pad1)") (class "Default")
      (node (ref "Optoacoplador1") (pin "1") (pinfunction "NC_1") (pintype "passive"))
    )
    (net (code "122") (name "unconnected-(Optoacoplador1-NC-Pad4)") (class "Default")
      (node (ref "Optoacoplador1") (pin "4") (pinfunction "NC_4") (pintype "passive"))
    )
    (net (code "123") (name "unconnected-(Optoacoplador2-NC-Pad1)") (class "Default")
      (node (ref "Optoacoplador2") (pin "1") (pinfunction "NC_1") (pintype "passive"))
    )
    (net (code "124") (name "unconnected-(Optoacoplador2-NC-Pad4)") (class "Default")
      (node (ref "Optoacoplador2") (pin "4") (pinfunction "NC_4") (pintype "passive"))
    )
    (net (code "125") (name "unconnected-(Optoacoplador3-NC-Pad1)") (class "Default")
      (node (ref "Optoacoplador3") (pin "1") (pinfunction "NC_1") (pintype "passive"))
    )
    (net (code "126") (name "unconnected-(Optoacoplador3-NC-Pad4)") (class "Default")
      (node (ref "Optoacoplador3") (pin "4") (pinfunction "NC_4") (pintype "passive"))
    )
    (net (code "127") (name "unconnected-(Optoacoplador4-NC-Pad1)") (class "Default")
      (node (ref "Optoacoplador4") (pin "1") (pinfunction "NC_1") (pintype "passive"))
    )
    (net (code "128") (name "unconnected-(Optoacoplador4-NC-Pad4)") (class "Default")
      (node (ref "Optoacoplador4") (pin "4") (pinfunction "NC_4") (pintype "passive"))
    )
    (net (code "129") (name "unconnected-(Optoacoplador5-NC-Pad1)") (class "Default")
      (node (ref "Optoacoplador5") (pin "1") (pinfunction "NC_1") (pintype "passive"))
    )
    (net (code "130") (name "unconnected-(Optoacoplador5-NC-Pad4)") (class "Default")
      (node (ref "Optoacoplador5") (pin "4") (pinfunction "NC_4") (pintype "passive"))
    )
    (net (code "131") (name "unconnected-(Optoacoplador6-NC-Pad1)") (class "Default")
      (node (ref "Optoacoplador6") (pin "1") (pinfunction "NC_1") (pintype "passive"))
    )
    (net (code "132") (name "unconnected-(Optoacoplador6-NC-Pad4)") (class "Default")
      (node (ref "Optoacoplador6") (pin "4") (pinfunction "NC_4") (pintype "passive"))
    )
    (net (code "133") (name "unconnected-(UART-Pad1)") (class "Default")
      (node (ref "UART") (pin "1") (pinfunction "1_1") (pintype "passive"))
    )
    (net (code "134") (name "unconnected-(UART-Pad5)") (class "Default")
      (node (ref "UART") (pin "5") (pinfunction "5_5") (pintype "passive"))
    )
  )
)
